# HV_PWR_STAGE.net
KiCad netlist of a schematic drawn in Altium Designer
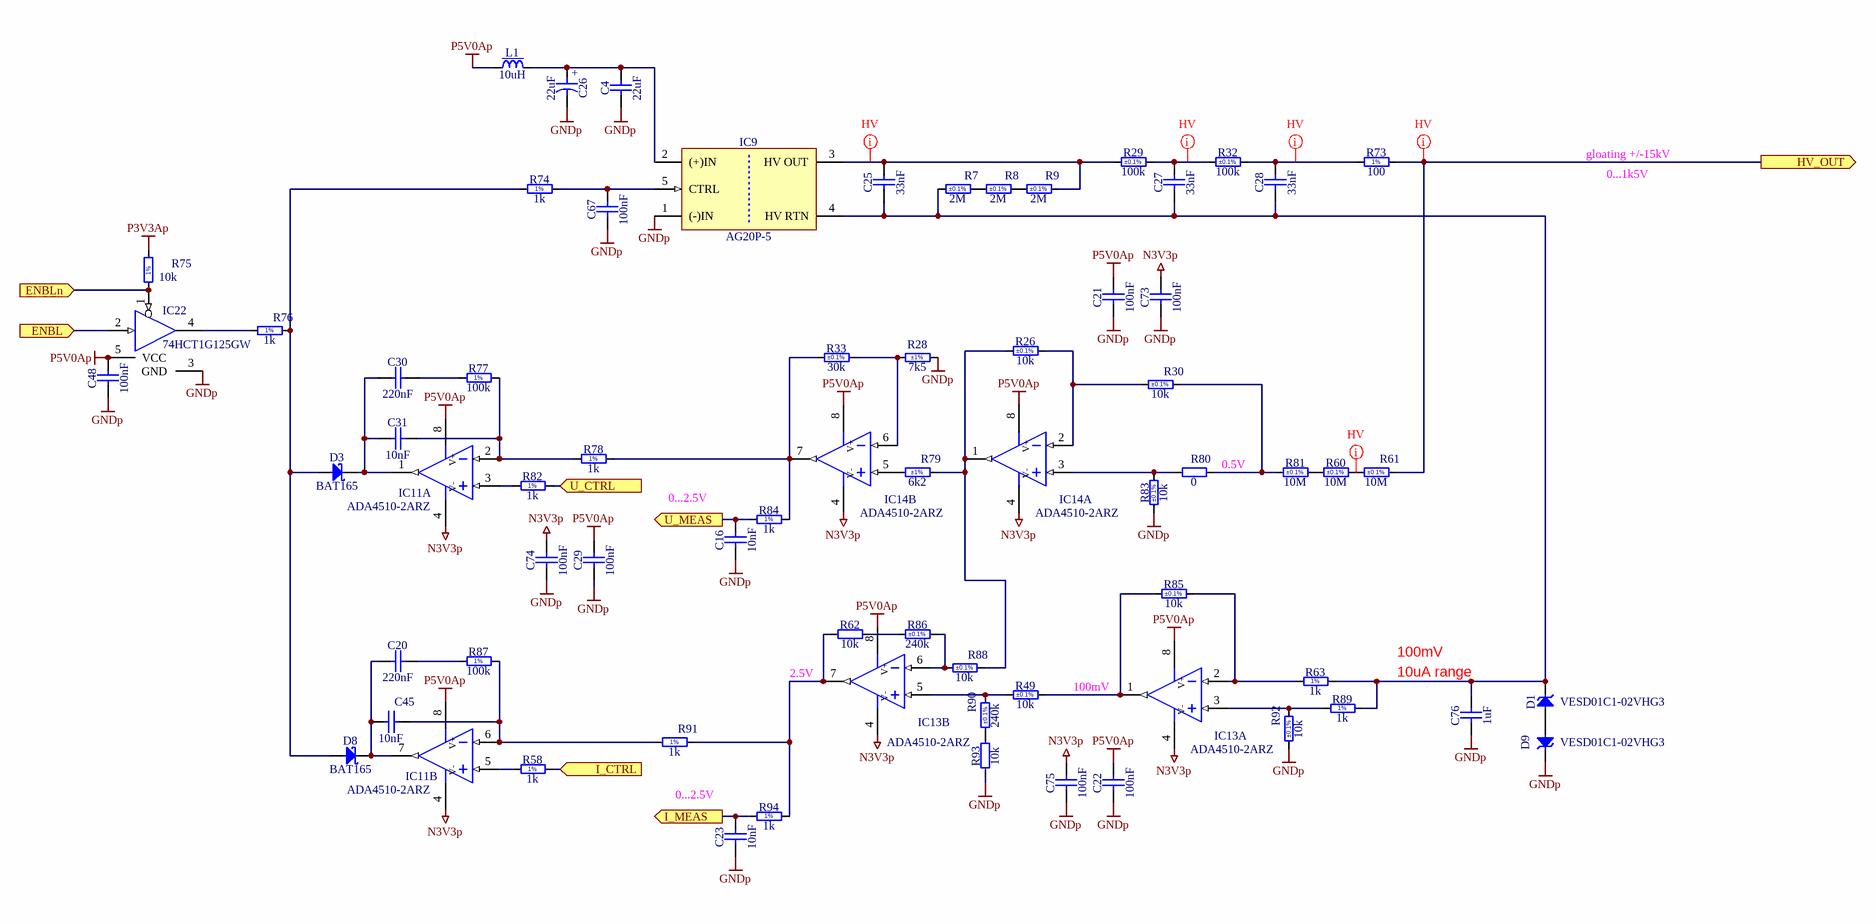
[diagram p0: HV_PWR_STAGE.SchDoc]

(export (version "E")
  (design (tool "Eeschema 10.0.6"))
  (components
    (comp (ref "C4")
      (value "22uF")
      (footprint "CAPC3216X180N")
      (description "Non-polarised capacitor")
      (fields
        (field (name "PART NUMBER") "CC1206_22UF_25V_20%_X5R")
        (field (name "VOLTAGE") "25V")
        (field (name "AUTHOR") "CERN DEM WB")
      )
      (libsource (lib "Capacitors") (part "Capacitor - non polarized"))
    )
    (comp (ref "C16")
      (value "10nF")
      (footprint "CAPC1005X55N")
      (description "Non-polarised capacitor")
      (fields
        (field (name "PART NUMBER") "CC0402_10NF_25V_10%_X7R")
        (field (name "VOLTAGE") "25V")
        (field (name "AUTHOR") "CERN DEM JLC")
      )
      (libsource (lib "Capacitors") (part "Capacitor - non polarized"))
    )
    (comp (ref "C20")
      (value "220nF")
      (footprint "CAPC1608X87N")
      (description "Non-polarised capacitor")
      (fields
        (field (name "PART NUMBER") "CC0603_220NF_10V_10%_X7R")
        (field (name "VOLTAGE") "10V")
        (field (name "AUTHOR") "CERN DEM JLC")
      )
      (libsource (lib "Capacitors") (part "Capacitor - non polarized"))
    )
    (comp (ref "C21")
      (value "100nF")
      (footprint "CAPC1005X55N")
      (description "Non-polarised capacitor")
      (fields
        (field (name "PART NUMBER") "CC0402_100NF_16V_10%_X7R")
        (field (name "VOLTAGE") "16V")
        (field (name "AUTHOR") "CERN DEM JLC")
      )
      (libsource (lib "Capacitors") (part "Capacitor - non polarized"))
    )
    (comp (ref "C22")
      (value "100nF")
      (footprint "CAPC1005X55N")
      (description "Non-polarised capacitor")
      (fields
        (field (name "PART NUMBER") "CC0402_100NF_16V_10%_X7R")
        (field (name "VOLTAGE") "16V")
        (field (name "AUTHOR") "CERN DEM JLC")
      )
      (libsource (lib "Capacitors") (part "Capacitor - non polarized"))
    )
    (comp (ref "C23")
      (value "10nF")
      (footprint "CAPC1005X55N")
      (description "Non-polarised capacitor")
      (fields
        (field (name "PART NUMBER") "CC0402_10NF_25V_10%_X7R")
        (field (name "VOLTAGE") "25V")
        (field (name "AUTHOR") "CERN DEM JLC")
      )
      (libsource (lib "Capacitors") (part "Capacitor - non polarized"))
    )
    (comp (ref "C25")
      (value "33nF")
      (footprint "CAPC5764X279N")
      (description "Non-polarised capacitor")
      (fields
        (field (name "PART NUMBER") "CC2225_33NF_2KV_10%_X7R")
        (field (name "VOLTAGE") "2KV")
        (field (name "AUTHOR") "CERN DEM JMW")
      )
      (libsource (lib "Capacitors") (part "Capacitor - non polarized"))
    )
    (comp (ref "C26")
      (value "22uF")
      (footprint "CAPMP3528X210N")
      (description "Polarised capacitor")
      (fields
        (field (name "PART NUMBER") "CTE3528-21_22UF_20V_10%")
        (field (name "VOLTAGE") "20V")
        (field (name "AUTHOR") "CERN DEM JLC")
      )
      (libsource (lib "Capacitors") (part "Capacitor - polarized"))
    )
    (comp (ref "C27")
      (value "33nF")
      (footprint "CAPC5764X279N")
      (description "Non-polarised capacitor")
      (fields
        (field (name "PART NUMBER") "CC2225_33NF_2KV_10%_X7R")
        (field (name "VOLTAGE") "2KV")
        (field (name "AUTHOR") "CERN DEM JMW")
      )
      (libsource (lib "Capacitors") (part "Capacitor - non polarized"))
    )
    (comp (ref "C28")
      (value "33nF")
      (footprint "CAPC5764X279N")
      (description "Non-polarised capacitor")
      (fields
        (field (name "PART NUMBER") "CC2225_33NF_2KV_10%_X7R")
        (field (name "VOLTAGE") "2KV")
        (field (name "AUTHOR") "CERN DEM JMW")
      )
      (libsource (lib "Capacitors") (part "Capacitor - non polarized"))
    )
    (comp (ref "C29")
      (value "100nF")
      (footprint "CAPC1005X55N")
      (description "Non-polarised capacitor")
      (fields
        (field (name "PART NUMBER") "CC0402_100NF_16V_10%_X7R")
        (field (name "VOLTAGE") "16V")
        (field (name "AUTHOR") "CERN DEM JLC")
      )
      (libsource (lib "Capacitors") (part "Capacitor - non polarized"))
    )
    (comp (ref "C30")
      (value "220nF")
      (footprint "CAPC1608X87N")
      (description "Non-polarised capacitor")
      (fields
        (field (name "PART NUMBER") "CC0603_220NF_10V_10%_X7R")
        (field (name "VOLTAGE") "10V")
        (field (name "AUTHOR") "CERN DEM JLC")
      )
      (libsource (lib "Capacitors") (part "Capacitor - non polarized"))
    )
    (comp (ref "C31")
      (value "10nF")
      (footprint "CAPC1608X87N")
      (description "Non-polarised capacitor")
      (fields
        (field (name "PART NUMBER") "CC0603_10NF_50V_5%_C0G")
        (field (name "VOLTAGE") "50V")
        (field (name "AUTHOR") "CERN DEM JLC")
      )
      (libsource (lib "Capacitors") (part "Capacitor - non polarized"))
    )
    (comp (ref "C45")
      (value "10nF")
      (footprint "CAPC1608X87N")
      (description "Non-polarised capacitor")
      (fields
        (field (name "PART NUMBER") "CC0603_10NF_50V_5%_C0G")
        (field (name "VOLTAGE") "50V")
        (field (name "AUTHOR") "CERN DEM JLC")
      )
      (libsource (lib "Capacitors") (part "Capacitor - non polarized"))
    )
    (comp (ref "C48")
      (value "100nF")
      (footprint "CAPC1005X55N")
      (description "Non-polarised capacitor")
      (fields
        (field (name "PART NUMBER") "CC0402_100NF_16V_10%_X7R")
        (field (name "VOLTAGE") "16V")
        (field (name "AUTHOR") "CERN DEM JLC")
      )
      (libsource (lib "Capacitors") (part "Capacitor - non polarized"))
    )
    (comp (ref "C67")
      (value "100nF")
      (footprint "CAPC1005X55N")
      (description "Non-polarised capacitor")
      (fields
        (field (name "PART NUMBER") "CC0402_100NF_16V_10%_X7R")
        (field (name "VOLTAGE") "16V")
        (field (name "AUTHOR") "CERN DEM JLC")
      )
      (libsource (lib "Capacitors") (part "Capacitor - non polarized"))
    )
    (comp (ref "C73")
      (value "100nF")
      (footprint "CAPC1005X55N")
      (description "Non-polarised capacitor")
      (fields
        (field (name "PART NUMBER") "CC0402_100NF_16V_10%_X7R")
        (field (name "VOLTAGE") "16V")
        (field (name "AUTHOR") "CERN DEM JLC")
      )
      (libsource (lib "Capacitors") (part "Capacitor - non polarized"))
    )
    (comp (ref "C74")
      (value "100nF")
      (footprint "CAPC1005X55N")
      (description "Non-polarised capacitor")
      (fields
        (field (name "PART NUMBER") "CC0402_100NF_16V_10%_X7R")
        (field (name "VOLTAGE") "16V")
        (field (name "AUTHOR") "CERN DEM JLC")
      )
      (libsource (lib "Capacitors") (part "Capacitor - non polarized"))
    )
    (comp (ref "C75")
      (value "100nF")
      (footprint "CAPC1005X55N")
      (description "Non-polarised capacitor")
      (fields
        (field (name "PART NUMBER") "CC0402_100NF_16V_10%_X7R")
        (field (name "VOLTAGE") "16V")
        (field (name "AUTHOR") "CERN DEM JLC")
      )
      (libsource (lib "Capacitors") (part "Capacitor - non polarized"))
    )
    (comp (ref "C76")
      (value "1uF")
      (footprint "CAPC1608X87N")
      (description "Non-polarised capacitor")
      (fields
        (field (name "PART NUMBER") "CC0603_1UF_16V_10%_X7R")
        (field (name "VOLTAGE") "16V")
        (field (name "AUTHOR") "CERN DEM JLC")
      )
      (libsource (lib "Capacitors") (part "Capacitor - non polarized"))
    )
    (comp (ref "D1")
      (value "VESD01C1-02VHG3")
      (footprint "SODFL1608X70N")
      (description "Transient Voltage Suppressor Diode (Uni-Directional)")
      (fields
        (field (name "VOLTAGE") "1V")
        (field (name "POWER") "100W")
        (field (name "AUTHOR") "CERN DEM BC")
      )
      (libsource (lib "ICs And Semiconductors") (part "Diode TVS Uni-Directional"))
    )
    (comp (ref "D3")
      (value "BAT165")
      (footprint "SOD2512X110N")
      (description "Schottky Diode")
      (fields
        (field (name "VOLTAGE") "40V")
        (field (name "POWER") "750mA")
        (field (name "AUTHOR") "CERN DEM JLC")
      )
      (libsource (lib "ICs And Semiconductors") (part "Diode Schottky"))
    )
    (comp (ref "D8")
      (value "BAT165")
      (footprint "SOD2512X110N")
      (description "Schottky Diode")
      (fields
        (field (name "VOLTAGE") "40V")
        (field (name "POWER") "750mA")
        (field (name "AUTHOR") "CERN DEM JLC")
      )
      (libsource (lib "ICs And Semiconductors") (part "Diode Schottky"))
    )
    (comp (ref "D9")
      (value "VESD01C1-02VHG3")
      (footprint "SODFL1608X70N")
      (description "Transient Voltage Suppressor Diode (Uni-Directional)")
      (fields
        (field (name "VOLTAGE") "1V")
        (field (name "POWER") "100W")
        (field (name "AUTHOR") "CERN DEM BC")
      )
      (libsource (lib "ICs And Semiconductors") (part "Diode TVS Uni-Directional"))
    )
    (comp (ref "IC9")
      (value "AG20P-5")
      (footprint "DCDC_XPPOWER_AG0-2KV")
      (description "XP POWER, AG Series, DC/HVDC Converter")
      (fields (field (name "MANUFACTURER") "XP POWER") (field (name "AUTHOR") "CERN DEM BC"))
      (libsource (lib "ICs And Semiconductors") (part "DCDC_XPPOWER_AG"))
    )
    (comp (ref "IC11")
      (value "ADA4510-2ARZ")
      (footprint "SOIC127P600X175-8N")
      (description "Precision, 40 V, ±70 nV/°C, Rail-to-Rail Input and Output Op Amp with DigiTrim")
      (fields (field (name "MANUFACTURER") "ANALOG DEVICES") (field (name "AUTHOR") "GK"))
      (libsource (lib "Amplifiers") (part "OA_ADA4510-2ARZ"))
    )
    (comp (ref "IC13")
      (value "ADA4510-2ARZ")
      (footprint "SOIC127P600X175-8N")
      (description "Precision, 40 V, ±70 nV/°C, Rail-to-Rail Input and Output Op Amp with DigiTrim")
      (fields (field (name "MANUFACTURER") "ANALOG DEVICES") (field (name "AUTHOR") "GK"))
      (libsource (lib "Amplifiers") (part "OA_ADA4510-2ARZ"))
    )
    (comp (ref "IC14")
      (value "ADA4510-2ARZ")
      (footprint "SOIC127P600X175-8N")
      (description "Precision, 40 V, ±70 nV/°C, Rail-to-Rail Input and Output Op Amp with DigiTrim")
      (fields (field (name "MANUFACTURER") "ANALOG DEVICES") (field (name "AUTHOR") "GK"))
      (libsource (lib "Amplifiers") (part "OA_ADA4510-2ARZ"))
    )
    (comp (ref "IC22")
      (value "74HCT1G125GW")
      (footprint "SOT65P210X110-5N")
      (description "Single Bus Buffer Gate With 3-State Output")
      (fields (field (name "MANUFACTURER") "NEXPERIA") (field (name "AUTHOR") "CERN DEM JMW"))
      (libsource (lib "ICs And Semiconductors") (part "741G125"))
    )
    (comp (ref "L1")
      (value "10uH")
      (footprint "IND_BOURNS_PM43")
      (description "Inductor With Core")
      (fields
        (field (name "PART NUMBER") "IND_10UH_20%_BOURNS_PM43")
        (field (name "POWER") "1.15A")
        (field (name "AUTHOR") "CERN DEM JLC")
      )
      (libsource (lib "Inductors & Transformers") (part "Inductor With Magnetic core"))
    )
    (comp (ref "R7")
      (value "2M")
      (footprint "RESC5025X65N")
      (description "RES, HV, 2010, 2 Mohm, 0.1%, 25 ppm, 1W")
      (fields
        (field (name "PART NUMBER") "R1210_2M0_0.1%_1/3W_25ppm")
        (field (name "POWER") "1/3W")
        (field (name "TOLERANCE") "±0.1%")
        (field (name "AUTHOR") "GK")
      )
      (libsource (lib "Passives_RC") (part "R1210_2M0_0.1%_1/3W_25ppm"))
    )
    (comp (ref "R8")
      (value "2M")
      (footprint "RESC5025X65N")
      (description "RES, HV, 2010, 2 Mohm, 0.1%, 25 ppm, 1W")
      (fields
        (field (name "PART NUMBER") "R1210_2M0_0.1%_1/3W_25ppm")
        (field (name "POWER") "1/3W")
        (field (name "TOLERANCE") "±0.1%")
        (field (name "AUTHOR") "GK")
      )
      (libsource (lib "Passives_RC") (part "R1210_2M0_0.1%_1/3W_25ppm"))
    )
    (comp (ref "R9")
      (value "2M")
      (footprint "RESC5025X65N")
      (description "RES, HV, 2010, 2 Mohm, 0.1%, 25 ppm, 1W")
      (fields
        (field (name "PART NUMBER") "R1210_2M0_0.1%_1/3W_25ppm")
        (field (name "POWER") "1/3W")
        (field (name "TOLERANCE") "±0.1%")
        (field (name "AUTHOR") "GK")
      )
      (libsource (lib "Passives_RC") (part "R1210_2M0_0.1%_1/3W_25ppm"))
    )
    (comp (ref "R26")
      (value "10k")
      (footprint "RESC1608X55N")
      (description "Resistor - 0.1%")
      (fields
        (field (name "TOLERANCE") "±0.1%")
        (field (name "PART NUMBER") "R0603_10K_0.1%_0.063W_10PPM")
        (field (name "POWER") "0.063W")
        (field (name "AUTHOR") "CERN DEM JLC")
      )
      (libsource (lib "Resistors") (part "Resistor - 0.1%"))
    )
    (comp (ref "R28")
      (value "7k5")
      (footprint "RESC1608X55N")
      (description "Resistor - 1%")
      (fields
        (field (name "TOLERANCE") "±1%")
        (field (name "PART NUMBER") "R0603_7K5_1%_0.1W_100PPM")
        (field (name "POWER") "0.1W")
        (field (name "AUTHOR") "CERN DEM JLC")
      )
      (libsource (lib "") (part "Resistor - 1%_1"))
    )
    (comp (ref "R29")
      (value "100k")
      (footprint "RESC3216X50N")
      (description "Resistor - 0.1%")
      (fields
        (field (name "TOLERANCE") "±0.1%")
        (field (name "PART NUMBER") "R1206_100K_0.1%_0.4W_25PPM_VISHAY_PAT")
        (field (name "POWER") "0.4W")
        (field (name "AUTHOR") "CERN DEM MR")
      )
      (libsource (lib "Resistors") (part "Resistor - 0.1%"))
    )
    (comp (ref "R30")
      (value "10k")
      (footprint "RESC1608X55N")
      (description "Resistor - 0.1%")
      (fields
        (field (name "TOLERANCE") "±0.1%")
        (field (name "PART NUMBER") "R0603_10K_0.1%_0.063W_10PPM")
        (field (name "POWER") "0.063W")
        (field (name "AUTHOR") "CERN DEM JLC")
      )
      (libsource (lib "Resistors") (part "Resistor - 0.1%"))
    )
    (comp (ref "R32")
      (value "100k")
      (footprint "RESC3216X50N")
      (description "Resistor - 0.1%")
      (fields
        (field (name "TOLERANCE") "±0.1%")
        (field (name "PART NUMBER") "R1206_100K_0.1%_0.4W_25PPM_VISHAY_PAT")
        (field (name "POWER") "0.4W")
        (field (name "AUTHOR") "CERN DEM MR")
      )
      (libsource (lib "Resistors") (part "Resistor - 0.1%"))
    )
    (comp (ref "R33")
      (value "30k")
      (footprint "RESC1608X55N")
      (description "Resistor - 0.1%")
      (fields
        (field (name "TOLERANCE") "±0.1%")
        (field (name "PART NUMBER") "R0603_30K_0.1%_0.063W_25PPM")
        (field (name "POWER") "0.063W")
        (field (name "AUTHOR") "CERN DEM JMW")
      )
      (libsource (lib "Resistors") (part "Resistor - 0.1%"))
    )
    (comp (ref "R49")
      (value "10k")
      (footprint "RESC1608X55N")
      (description "Resistor - 0.1%")
      (fields
        (field (name "TOLERANCE") "±0.1%")
        (field (name "PART NUMBER") "R0603_10K_0.1%_0.063W_10PPM")
        (field (name "POWER") "0.063W")
        (field (name "AUTHOR") "CERN DEM JLC")
      )
      (libsource (lib "Resistors") (part "Resistor - 0.1%"))
    )
    (comp (ref "R58")
      (value "1k")
      (footprint "RESC1005X40N")
      (description "Resistor - 1%")
      (fields
        (field (name "PART NUMBER") "R0402_1K_1%_0.0625W_100PPM")
        (field (name "POWER") "0.0625W")
        (field (name "AUTHOR") "CERN DEM JLC")
      )
      (libsource (lib "Resistors") (part "Resistor - 1%"))
    )
    (comp (ref "R60")
      (value "10M")
      (footprint "RESC5025X65N")
      (description "RES, HV, 2010, 10 Mohm, 0.1%, 25 ppm, 1W")
      (fields
        (field (name "PART NUMBER") "R1210_1M0_0.1%_1W_25ppm_HVCB2010BDE10M0")
        (field (name "POWER") "1W")
        (field (name "TOLERANCE") "±0.1%")
        (field (name "AUTHOR") "GK")
      )
      (libsource (lib "Passives_RC") (part "R1210_1M0_0.1%_1W_25ppm_HVCB2010BDE10M0"))
    )
    (comp (ref "R61")
      (value "10M")
      (footprint "RESC5025X65N")
      (description "RES, HV, 2010, 10 Mohm, 0.1%, 25 ppm, 1W")
      (fields
        (field (name "PART NUMBER") "R1210_1M0_0.1%_1W_25ppm_HVCB2010BDE10M0")
        (field (name "POWER") "1W")
        (field (name "TOLERANCE") "±0.1%")
        (field (name "AUTHOR") "GK")
      )
      (libsource (lib "Passives_RC") (part "R1210_1M0_0.1%_1W_25ppm_HVCB2010BDE10M0"))
    )
    (comp (ref "R62")
      (value "10k")
      (footprint "RESC1005X40N")
      (description "Resistor - 1%")
      (fields
        (field (name "PART NUMBER") "R0402_10K_1%_0.0625W_100PPM")
        (field (name "POWER") "0.0625W")
        (field (name "AUTHOR") "CERN DEM JLC")
      )
      (libsource (lib "Resistors") (part "Resistor - 1%"))
    )
    (comp (ref "R63")
      (value "1k")
      (footprint "RESC1005X40N")
      (description "Resistor - 1%")
      (fields
        (field (name "PART NUMBER") "R0402_1K_1%_0.0625W_100PPM")
        (field (name "POWER") "0.0625W")
        (field (name "AUTHOR") "CERN DEM JLC")
      )
      (libsource (lib "Resistors") (part "Resistor - 1%"))
    )
    (comp (ref "R73")
      (value "100")
      (footprint "RESC6331X70N")
      (description "Resistor - 1%")
      (fields
        (field (name "PART NUMBER") "R2512_100R_1%_1.5W_100PPM_VISHAY_CRCW-HP e3")
        (field (name "POWER") "1.5W")
        (field (name "AUTHOR") "CERN DEM JLC")
      )
      (libsource (lib "Resistors") (part "Resistor - 1%"))
    )
    (comp (ref "R74")
      (value "1k")
      (footprint "RESC1608X55N")
      (description "Resistor - 1%")
      (fields
        (field (name "PART NUMBER") "R0603_1K_1%_0.1W_100PPM")
        (field (name "POWER") "0.1W")
        (field (name "AUTHOR") "CERN DEM JLC")
      )
      (libsource (lib "Resistors") (part "Resistor - 1%"))
    )
    (comp (ref "R75")
      (value "10k")
      (footprint "RESC1005X40N")
      (description "Resistor - 1%")
      (fields
        (field (name "PART NUMBER") "R0402_10K_1%_0.0625W_100PPM")
        (field (name "POWER") "0.0625W")
        (field (name "AUTHOR") "CERN DEM JLC")
      )
      (libsource (lib "Resistors") (part "Resistor - 1%"))
    )
    (comp (ref "R76")
      (value "1k")
      (footprint "RESC1005X40N")
      (description "Resistor - 1%")
      (fields
        (field (name "PART NUMBER") "R0402_1K_1%_0.0625W_100PPM")
        (field (name "POWER") "0.0625W")
        (field (name "AUTHOR") "CERN DEM JLC")
      )
      (libsource (lib "Resistors") (part "Resistor - 1%"))
    )
    (comp (ref "R77")
      (value "100k")
      (footprint "RESC1608X55N")
      (description "Resistor - 1%")
      (fields
        (field (name "PART NUMBER") "R0603_100K_1%_0.1W_100PPM")
        (field (name "POWER") "0.1W")
        (field (name "AUTHOR") "CERN DEM JLC")
      )
      (libsource (lib "Resistors") (part "Resistor - 1%"))
    )
    (comp (ref "R78")
      (value "1k")
      (footprint "RESC1005X40N")
      (description "Resistor - 1%")
      (fields
        (field (name "PART NUMBER") "R0402_1K_1%_0.0625W_100PPM")
        (field (name "POWER") "0.0625W")
        (field (name "AUTHOR") "CERN DEM JLC")
      )
      (libsource (lib "Resistors") (part "Resistor - 1%"))
    )
    (comp (ref "R79")
      (value "6k2")
      (footprint "RESC1608X55N")
      (description "Resistor - 1%")
      (fields
        (field (name "TOLERANCE") "±1%")
        (field (name "PART NUMBER") "R0603_6K2_1%_0.1W_100PPM")
        (field (name "POWER") "0.1W")
        (field (name "AUTHOR") "CERN DEM JLC")
      )
      (libsource (lib "") (part "Resistor - 1%_1"))
    )
    (comp (ref "R80")
      (value "0")
      (footprint "RESC1005X40N")
      (description "Resistor")
      (fields
        (field (name "PART NUMBER") "R0402_0R_JUMPER")
        (field (name "MANUFACTURER") "GENERIC")
        (field (name "AUTHOR") "CERN DEM JLC")
      )
      (libsource (lib "Resistors") (part "Resistor"))
    )
    (comp (ref "R81")
      (value "10M")
      (footprint "RESC5025X65N")
      (description "RES, HV, 2010, 10 Mohm, 0.1%, 25 ppm, 1W")
      (fields
        (field (name "PART NUMBER") "R1210_1M0_0.1%_1W_25ppm_HVCB2010BDE10M0")
        (field (name "POWER") "1W")
        (field (name "TOLERANCE") "±0.1%")
        (field (name "AUTHOR") "GK")
      )
      (libsource (lib "Passives_RC") (part "R1210_1M0_0.1%_1W_25ppm_HVCB2010BDE10M0"))
    )
    (comp (ref "R82")
      (value "1k")
      (footprint "RESC1005X40N")
      (description "Resistor - 1%")
      (fields
        (field (name "PART NUMBER") "R0402_1K_1%_0.0625W_100PPM")
        (field (name "POWER") "0.0625W")
        (field (name "AUTHOR") "CERN DEM JLC")
      )
      (libsource (lib "Resistors") (part "Resistor - 1%"))
    )
    (comp (ref "R83")
      (value "10k")
      (footprint "RESC1608X55N")
      (description "Resistor - 0.1%")
      (fields
        (field (name "TOLERANCE") "±0.1%")
        (field (name "PART NUMBER") "R0603_10K_0.1%_0.063W_10PPM")
        (field (name "POWER") "0.063W")
        (field (name "AUTHOR") "CERN DEM JLC")
      )
      (libsource (lib "Resistors") (part "Resistor - 0.1%"))
    )
    (comp (ref "R84")
      (value "1k")
      (footprint "RESC1005X40N")
      (description "Resistor - 1%")
      (fields
        (field (name "PART NUMBER") "R0402_1K_1%_0.0625W_100PPM")
        (field (name "POWER") "0.0625W")
        (field (name "AUTHOR") "CERN DEM JLC")
      )
      (libsource (lib "Resistors") (part "Resistor - 1%"))
    )
    (comp (ref "R85")
      (value "10k")
      (footprint "RESC1608X55N")
      (description "Resistor - 0.1%")
      (fields
        (field (name "TOLERANCE") "±0.1%")
        (field (name "PART NUMBER") "R0603_10K_0.1%_0.063W_10PPM")
        (field (name "POWER") "0.063W")
        (field (name "AUTHOR") "CERN DEM JLC")
      )
      (libsource (lib "Resistors") (part "Resistor - 0.1%"))
    )
    (comp (ref "R86")
      (value "240k")
      (footprint "RESC1608X55N")
      (description "Resistor - 0.1%")
      (fields
        (field (name "TOLERANCE") "±0.1%")
        (field (name "PART NUMBER") "R0603_240K_0.1%_0.063W_10PPM")
        (field (name "POWER") "0.063W")
        (field (name "AUTHOR") "CERN DEM BC")
      )
      (libsource (lib "Resistors") (part "Resistor - 0.1%"))
    )
    (comp (ref "R87")
      (value "100k")
      (footprint "RESC1608X55N")
      (description "Resistor - 1%")
      (fields
        (field (name "PART NUMBER") "R0603_100K_1%_0.1W_100PPM")
        (field (name "POWER") "0.1W")
        (field (name "AUTHOR") "CERN DEM JLC")
      )
      (libsource (lib "Resistors") (part "Resistor - 1%"))
    )
    (comp (ref "R88")
      (value "10k")
      (footprint "RESC1608X55N")
      (description "Resistor - 0.1%")
      (fields
        (field (name "TOLERANCE") "±0.1%")
        (field (name "PART NUMBER") "R0603_10K_0.1%_0.063W_10PPM")
        (field (name "POWER") "0.063W")
        (field (name "AUTHOR") "CERN DEM JLC")
      )
      (libsource (lib "Resistors") (part "Resistor - 0.1%"))
    )
    (comp (ref "R89")
      (value "1k")
      (footprint "RESC1005X40N")
      (description "Resistor - 1%")
      (fields
        (field (name "PART NUMBER") "R0402_1K_1%_0.0625W_100PPM")
        (field (name "POWER") "0.0625W")
        (field (name "AUTHOR") "CERN DEM JLC")
      )
      (libsource (lib "Resistors") (part "Resistor - 1%"))
    )
    (comp (ref "R90")
      (value "240k")
      (footprint "RESC1608X55N")
      (description "Resistor - 0.1%")
      (fields
        (field (name "TOLERANCE") "±0.1%")
        (field (name "PART NUMBER") "R0603_240K_0.1%_0.063W_10PPM")
        (field (name "POWER") "0.063W")
        (field (name "AUTHOR") "CERN DEM BC")
      )
      (libsource (lib "Resistors") (part "Resistor - 0.1%"))
    )
    (comp (ref "R91")
      (value "1k")
      (footprint "RESC1005X40N")
      (description "Resistor - 1%")
      (fields
        (field (name "PART NUMBER") "R0402_1K_1%_0.0625W_100PPM")
        (field (name "POWER") "0.0625W")
        (field (name "AUTHOR") "CERN DEM JLC")
      )
      (libsource (lib "Resistors") (part "Resistor - 1%"))
    )
    (comp (ref "R92")
      (value "10k")
      (footprint "RESC1608X55N")
      (description "Resistor - 0.1%")
      (fields
        (field (name "TOLERANCE") "±0.1%")
        (field (name "PART NUMBER") "R0603_10K_0.1%_0.063W_10PPM")
        (field (name "POWER") "0.063W")
        (field (name "AUTHOR") "CERN DEM JLC")
      )
      (libsource (lib "Resistors") (part "Resistor - 0.1%"))
    )
    (comp (ref "R93")
      (value "10k")
      (footprint "RESC1005X40N")
      (description "Resistor - 1%")
      (fields
        (field (name "PART NUMBER") "R0402_10K_1%_0.0625W_100PPM")
        (field (name "POWER") "0.0625W")
        (field (name "AUTHOR") "CERN DEM JLC")
      )
      (libsource (lib "Resistors") (part "Resistor - 1%"))
    )
    (comp (ref "R94")
      (value "1k")
      (footprint "RESC1005X40N")
      (description "Resistor - 1%")
      (fields
        (field (name "PART NUMBER") "R0402_1K_1%_0.0625W_100PPM")
        (field (name "POWER") "0.0625W")
        (field (name "AUTHOR") "CERN DEM JLC")
      )
      (libsource (lib "Resistors") (part "Resistor - 1%"))
    )
  )
  (nets
    (net (code "1") (name "/ENBL") (class "Default")
      (node (ref "IC22") (pin "2") (pinfunction "IN_2") (pintype "input"))
    )
    (net (code "2") (name "/ENBLn") (class "Default")
      (node (ref "IC22") (pin "1") (pinfunction "~{G}_1") (pintype "input"))
      (node (ref "R75") (pin "1") (pinfunction "1_1") (pintype "passive"))
    )
    (net (code "3") (name "/HV_OUT") (class "Default")
      (node (ref "R61") (pin "2") (pinfunction "2_2") (pintype "passive"))
      (node (ref "R73") (pin "2") (pinfunction "2_2") (pintype "passive"))
    )
    (net (code "4") (name "/I_CTRL") (class "Default")
      (node (ref "R58") (pin "2") (pinfunction "2_2") (pintype "passive"))
    )
    (net (code "5") (name "/I_MEAS") (class "Default")
      (node (ref "C23") (pin "2") (pinfunction "2_2") (pintype "passive"))
      (node (ref "R94") (pin "1") (pinfunction "1_1") (pintype "passive"))
    )
    (net (code "6") (name "/U_CTRL") (class "Default")
      (node (ref "R82") (pin "2") (pinfunction "2_2") (pintype "passive"))
    )
    (net (code "7") (name "/U_MEAS") (class "Default")
      (node (ref "C16") (pin "2") (pinfunction "2_2") (pintype "passive"))
      (node (ref "R84") (pin "1") (pinfunction "1_1") (pintype "passive"))
    )
    (net (code "8") (name "GNDp") (class "Default")
      (node (ref "C16") (pin "1") (pinfunction "1_1") (pintype "passive"))
      (node (ref "C21") (pin "1") (pinfunction "1_1") (pintype "passive"))
      (node (ref "C22") (pin "1") (pinfunction "1_1") (pintype "passive"))
      (node (ref "C23") (pin "1") (pinfunction "1_1") (pintype "passive"))
      (node (ref "C26") (pin "2") (pinfunction "2_2") (pintype "passive"))
      (node (ref "C29") (pin "1") (pinfunction "1_1") (pintype "passive"))
      (node (ref "C4") (pin "1") (pinfunction "1_1") (pintype "passive"))
      (node (ref "C48") (pin "1") (pinfunction "1_1") (pintype "passive"))
      (node (ref "C67") (pin "1") (pinfunction "1_1") (pintype "passive"))
      (node (ref "C73") (pin "1") (pinfunction "1_1") (pintype "passive"))
      (node (ref "C74") (pin "1") (pinfunction "1_1") (pintype "passive"))
      (node (ref "C75") (pin "1") (pinfunction "1_1") (pintype "passive"))
      (node (ref "C76") (pin "1") (pinfunction "1_1") (pintype "passive"))
      (node (ref "D9") (pin "1") (pinfunction "C_1") (pintype "passive"))
      (node (ref "IC22") (pin "3") (pinfunction "GND_3") (pintype "power_in"))
      (node (ref "IC9") (pin "1") (pinfunction "(-)IN_1") (pintype "power_in"))
      (node (ref "R28") (pin "2") (pinfunction "2_2") (pintype "passive"))
      (node (ref "R83") (pin "1") (pinfunction "1_1") (pintype "passive"))
      (node (ref "R92") (pin "1") (pinfunction "1_1") (pintype "passive"))
      (node (ref "R93") (pin "1") (pinfunction "1_1") (pintype "passive"))
    )
    (net (code "9") (name "N3V3p") (class "Default")
      (node (ref "C73") (pin "2") (pinfunction "2_2") (pintype "passive"))
      (node (ref "C74") (pin "2") (pinfunction "2_2") (pintype "passive"))
      (node (ref "C75") (pin "2") (pinfunction "2_2") (pintype "passive"))
      (node (ref "IC11") (pin "4") (pinfunction "V-_4") (pintype "power_in"))
      (node (ref "IC13") (pin "4") (pinfunction "V-_4") (pintype "power_in"))
      (node (ref "IC14") (pin "4") (pinfunction "V-_4") (pintype "power_in"))
    )
    (net (code "10") (name "Net-(C20-Pad2)") (class "Default")
      (node (ref "C20") (pin "2") (pinfunction "2_2") (pintype "passive"))
      (node (ref "R87") (pin "1") (pinfunction "1_1") (pintype "passive"))
    )
    (net (code "11") (name "Net-(C27-Pad2)") (class "Default")
      (node (ref "C27") (pin "2") (pinfunction "2_2") (pintype "passive"))
      (node (ref "R29") (pin "2") (pinfunction "2_2") (pintype "passive"))
      (node (ref "R32") (pin "1") (pinfunction "1_1") (pintype "passive"))
    )
    (net (code "12") (name "Net-(C28-Pad2)") (class "Default")
      (node (ref "C28") (pin "2") (pinfunction "2_2") (pintype "passive"))
      (node (ref "R32") (pin "2") (pinfunction "2_2") (pintype "passive"))
      (node (ref "R73") (pin "1") (pinfunction "1_1") (pintype "passive"))
    )
    (net (code "13") (name "Net-(C30-Pad2)") (class "Default")
      (node (ref "C30") (pin "2") (pinfunction "2_2") (pintype "passive"))
      (node (ref "R77") (pin "1") (pinfunction "1_1") (pintype "passive"))
    )
    (net (code "14") (name "Net-(D1-A)") (class "Default")
      (node (ref "D1") (pin "2") (pinfunction "A_2") (pintype "passive"))
      (node (ref "D9") (pin "2") (pinfunction "A_2") (pintype "passive"))
    )
    (net (code "15") (name "Net-(D1-C)") (class "Default")
      (node (ref "C25") (pin "1") (pinfunction "1_1") (pintype "passive"))
      (node (ref "C27") (pin "1") (pinfunction "1_1") (pintype "passive"))
      (node (ref "C28") (pin "1") (pinfunction "1_1") (pintype "passive"))
      (node (ref "C76") (pin "2") (pinfunction "2_2") (pintype "passive"))
      (node (ref "D1") (pin "1") (pinfunction "C_1") (pintype "passive"))
      (node (ref "IC9") (pin "4") (pinfunction "HV_RTN_4") (pintype "power_in"))
      (node (ref "R63") (pin "2") (pinfunction "2_2") (pintype "passive"))
      (node (ref "R7") (pin "1") (pinfunction "1_1") (pintype "passive"))
      (node (ref "R89") (pin "2") (pinfunction "2_2") (pintype "passive"))
    )
    (net (code "16") (name "Net-(D3-A)") (class "Default")
      (node (ref "D3") (pin "2") (pinfunction "A_2") (pintype "passive"))
      (node (ref "D8") (pin "2") (pinfunction "A_2") (pintype "passive"))
      (node (ref "R74") (pin "1") (pinfunction "1_1") (pintype "passive"))
      (node (ref "R76") (pin "2") (pinfunction "2_2") (pintype "passive"))
    )
    (net (code "17") (name "Net-(D3-C)") (class "Default")
      (node (ref "C30") (pin "1") (pinfunction "1_1") (pintype "passive"))
      (node (ref "C31") (pin "1") (pinfunction "1_1") (pintype "passive"))
      (node (ref "D3") (pin "1") (pinfunction "C_1") (pintype "passive"))
      (node (ref "IC11") (pin "1") (pinfunction "OUT_1") (pintype "output"))
    )
    (net (code "18") (name "Net-(D8-C)") (class "Default")
      (node (ref "C20") (pin "1") (pinfunction "1_1") (pintype "passive"))
      (node (ref "C45") (pin "1") (pinfunction "1_1") (pintype "passive"))
      (node (ref "D8") (pin "1") (pinfunction "C_1") (pintype "passive"))
      (node (ref "IC11") (pin "7") (pinfunction "OUT_7") (pintype "output"))
    )
    (net (code "19") (name "Net-(IC9-(+)IN)") (class "Default")
      (node (ref "C26") (pin "1") (pinfunction "1_1") (pintype "passive"))
      (node (ref "C4") (pin "2") (pinfunction "2_2") (pintype "passive"))
      (node (ref "IC9") (pin "2") (pinfunction "(+)IN_2") (pintype "power_in"))
      (node (ref "L1") (pin "2") (pinfunction "2_2") (pintype "passive"))
    )
    (net (code "20") (name "Net-(IC9-CTRL)") (class "Default")
      (node (ref "C67") (pin "2") (pinfunction "2_2") (pintype "passive"))
      (node (ref "IC9") (pin "5") (pinfunction "CTRL_5") (pintype "input"))
      (node (ref "R74") (pin "2") (pinfunction "2_2") (pintype "passive"))
    )
    (net (code "21") (name "Net-(IC9-HV_OUT)") (class "Default")
      (node (ref "C25") (pin "2") (pinfunction "2_2") (pintype "passive"))
      (node (ref "IC9") (pin "3") (pinfunction "HV_OUT_3") (pintype "power_in"))
      (node (ref "R29") (pin "1") (pinfunction "1_1") (pintype "passive"))
      (node (ref "R9") (pin "2") (pinfunction "2_2") (pintype "passive"))
    )
    (net (code "22") (name "Net-(IC11A-IN+)") (class "Default")
      (node (ref "IC11") (pin "3") (pinfunction "IN+_3") (pintype "input"))
      (node (ref "R82") (pin "1") (pinfunction "1_1") (pintype "passive"))
    )
    (net (code "23") (name "Net-(IC11A-IN-)") (class "Default")
      (node (ref "C31") (pin "2") (pinfunction "2_2") (pintype "passive"))
      (node (ref "IC11") (pin "2") (pinfunction "IN-_2") (pintype "input"))
      (node (ref "R77") (pin "2") (pinfunction "2_2") (pintype "passive"))
      (node (ref "R78") (pin "1") (pinfunction "1_1") (pintype "passive"))
    )
    (net (code "24") (name "Net-(IC11B-IN+)") (class "Default")
      (node (ref "IC11") (pin "5") (pinfunction "IN+_5") (pintype "input"))
      (node (ref "R58") (pin "1") (pinfunction "1_1") (pintype "passive"))
    )
    (net (code "25") (name "Net-(IC11B-IN-)") (class "Default")
      (node (ref "C45") (pin "2") (pinfunction "2_2") (pintype "passive"))
      (node (ref "IC11") (pin "6") (pinfunction "IN-_6") (pintype "input"))
      (node (ref "R87") (pin "2") (pinfunction "2_2") (pintype "passive"))
      (node (ref "R91") (pin "1") (pinfunction "1_1") (pintype "passive"))
    )
    (net (code "26") (name "Net-(IC13A-IN+)") (class "Default")
      (node (ref "IC13") (pin "3") (pinfunction "IN+_3") (pintype "input"))
      (node (ref "R89") (pin "1") (pinfunction "1_1") (pintype "passive"))
      (node (ref "R92") (pin "2") (pinfunction "2_2") (pintype "passive"))
    )
    (net (code "27") (name "Net-(IC13A-IN-)") (class "Default")
      (node (ref "IC13") (pin "2") (pinfunction "IN-_2") (pintype "input"))
      (node (ref "R63") (pin "1") (pinfunction "1_1") (pintype "passive"))
      (node (ref "R85") (pin "2") (pinfunction "2_2") (pintype "passive"))
    )
    (net (code "28") (name "Net-(IC13A-OUT)") (class "Default")
      (node (ref "IC13") (pin "1") (pinfunction "OUT_1") (pintype "output"))
      (node (ref "R49") (pin "2") (pinfunction "2_2") (pintype "passive"))
      (node (ref "R85") (pin "1") (pinfunction "1_1") (pintype "passive"))
    )
    (net (code "29") (name "Net-(IC13B-IN+)") (class "Default")
      (node (ref "IC13") (pin "5") (pinfunction "IN+_5") (pintype "input"))
      (node (ref "R49") (pin "1") (pinfunction "1_1") (pintype "passive"))
      (node (ref "R90") (pin "2") (pinfunction "2_2") (pintype "passive"))
    )
    (net (code "30") (name "Net-(IC13B-IN-)") (class "Default")
      (node (ref "IC13") (pin "6") (pinfunction "IN-_6") (pintype "input"))
      (node (ref "R86") (pin "2") (pinfunction "2_2") (pintype "passive"))
      (node (ref "R88") (pin "1") (pinfunction "1_1") (pintype "passive"))
    )
    (net (code "31") (name "Net-(IC13B-OUT)") (class "Default")
      (node (ref "IC13") (pin "7") (pinfunction "OUT_7") (pintype "output"))
      (node (ref "R62") (pin "1") (pinfunction "1_1") (pintype "passive"))
      (node (ref "R91") (pin "2") (pinfunction "2_2") (pintype "passive"))
      (node (ref "R94") (pin "2") (pinfunction "2_2") (pintype "passive"))
    )
    (net (code "32") (name "Net-(IC14A-IN+)") (class "Default")
      (node (ref "IC14") (pin "3") (pinfunction "IN+_3") (pintype "input"))
      (node (ref "R80") (pin "1") (pinfunction "1_1") (pintype "passive"))
      (node (ref "R83") (pin "2") (pinfunction "2_2") (pintype "passive"))
    )
    (net (code "33") (name "Net-(IC14A-IN-)") (class "Default")
      (node (ref "IC14") (pin "2") (pinfunction "IN-_2") (pintype "input"))
      (node (ref "R26") (pin "2") (pinfunction "2_2") (pintype "passive"))
      (node (ref "R30") (pin "1") (pinfunction "1_1") (pintype "passive"))
    )
    (net (code "34") (name "Net-(IC14A-OUT)") (class "Default")
      (node (ref "IC14") (pin "1") (pinfunction "OUT_1") (pintype "output"))
      (node (ref "R26") (pin "1") (pinfunction "1_1") (pintype "passive"))
      (node (ref "R79") (pin "2") (pinfunction "2_2") (pintype "passive"))
      (node (ref "R88") (pin "2") (pinfunction "2_2") (pintype "passive"))
    )
    (net (code "35") (name "Net-(IC14B-IN+)") (class "Default")
      (node (ref "IC14") (pin "5") (pinfunction "IN+_5") (pintype "input"))
      (node (ref "R79") (pin "1") (pinfunction "1_1") (pintype "passive"))
    )
    (net (code "36") (name "Net-(IC14B-IN-)") (class "Default")
      (node (ref "IC14") (pin "6") (pinfunction "IN-_6") (pintype "input"))
      (node (ref "R28") (pin "1") (pinfunction "1_1") (pintype "passive"))
      (node (ref "R33") (pin "2") (pinfunction "2_2") (pintype "passive"))
    )
    (net (code "37") (name "Net-(IC14B-OUT)") (class "Default")
      (node (ref "IC14") (pin "7") (pinfunction "OUT_7") (pintype "output"))
      (node (ref "R33") (pin "1") (pinfunction "1_1") (pintype "passive"))
      (node (ref "R78") (pin "2") (pinfunction "2_2") (pintype "passive"))
      (node (ref "R84") (pin "2") (pinfunction "2_2") (pintype "passive"))
    )
    (net (code "38") (name "Net-(IC22-OUT)") (class "Default")
      (node (ref "IC22") (pin "4") (pinfunction "OUT_4") (pintype "tri_state"))
      (node (ref "R76") (pin "1") (pinfunction "1_1") (pintype "passive"))
    )
    (net (code "39") (name "Net-(R7-Pad2)") (class "Default")
      (node (ref "R7") (pin "2") (pinfunction "2_2") (pintype "passive"))
      (node (ref "R8") (pin "1") (pinfunction "1_1") (pintype "passive"))
    )
    (net (code "40") (name "Net-(R8-Pad2)") (class "Default")
      (node (ref "R8") (pin "2") (pinfunction "2_2") (pintype "passive"))
      (node (ref "R9") (pin "1") (pinfunction "1_1") (pintype "passive"))
    )
    (net (code "41") (name "Net-(R30-Pad2)") (class "Default")
      (node (ref "R30") (pin "2") (pinfunction "2_2") (pintype "passive"))
      (node (ref "R80") (pin "2") (pinfunction "2_2") (pintype "passive"))
      (node (ref "R81") (pin "1") (pinfunction "1_1") (pintype "passive"))
    )
    (net (code "42") (name "Net-(R60-Pad1)") (class "Default")
      (node (ref "R60") (pin "1") (pinfunction "1_1") (pintype "passive"))
      (node (ref "R81") (pin "2") (pinfunction "2_2") (pintype "passive"))
    )
    (net (code "43") (name "Net-(R60-Pad2)") (class "Default")
      (node (ref "R60") (pin "2") (pinfunction "2_2") (pintype "passive"))
      (node (ref "R61") (pin "1") (pinfunction "1_1") (pintype "passive"))
    )
    (net (code "44") (name "Net-(R62-Pad2)") (class "Default")
      (node (ref "R62") (pin "2") (pinfunction "2_2") (pintype "passive"))
      (node (ref "R86") (pin "1") (pinfunction "1_1") (pintype "passive"))
    )
    (net (code "45") (name "Net-(R90-Pad1)") (class "Default")
      (node (ref "R90") (pin "1") (pinfunction "1_1") (pintype "passive"))
      (node (ref "R93") (pin "2") (pinfunction "2_2") (pintype "passive"))
    )
    (net (code "46") (name "P3V3Ap") (class "Default")
      (node (ref "R75") (pin "2") (pinfunction "2_2") (pintype "passive"))
    )
    (net (code "47") (name "P5V0Ap") (class "Default")
      (node (ref "C21") (pin "2") (pinfunction "2_2") (pintype "passive"))
      (node (ref "C22") (pin "2") (pinfunction "2_2") (pintype "passive"))
      (node (ref "C29") (pin "2") (pinfunction "2_2") (pintype "passive"))
      (node (ref "C48") (pin "2") (pinfunction "2_2") (pintype "passive"))
      (node (ref "IC11") (pin "8") (pinfunction "V+_8") (pintype "power_in"))
      (node (ref "IC13") (pin "8") (pinfunction "V+_8") (pintype "power_in"))
      (node (ref "IC14") (pin "8") (pinfunction "V+_8") (pintype "power_in"))
      (node (ref "IC22") (pin "5") (pinfunction "VCC_5") (pintype "power_in"))
      (node (ref "L1") (pin "1") (pinfunction "1_1") (pintype "passive"))
    )
  )
)
